# SWJ_v1_0.net
KiCad netlist of a schematic drawn in Altium Designer
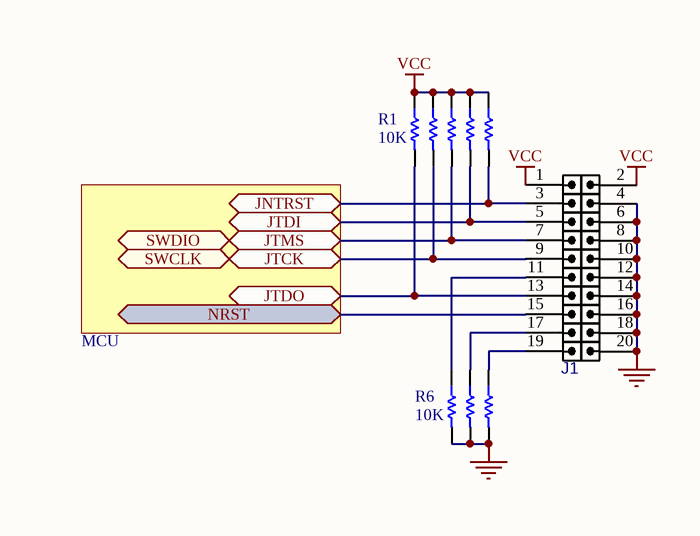
[diagram p0: SWJ_v1.0.SchDoc]

(export (version "E")
  (design (tool "Eeschema 10.0.6"))
  (components
    (comp (ref "J1")
      (value "Connector_2x10Pin_Male")
      (footprint "IDC_THD_P2.54_2X10")
      (description "Connector, Header")
      (fields (field (name "1_PART NUMBER") "TST-115-04-G-D-RA"))
      (libsource (lib "Connector") (part "Connector_2x10Pin_Male"))
    )
    (comp (ref "R1")
      (value "10K")
      (footprint "SMD_0805")
      (description "Resistor, 1/4W, 5%")
      (libsource (lib "General") (part "Resistor"))
    )
    (comp (ref "R2")
      (value "10K")
      (footprint "SMD_0805")
      (description "Resistor, 1/4W, 5%")
      (libsource (lib "General") (part "Resistor"))
    )
    (comp (ref "R3")
      (value "10K")
      (footprint "SMD_0805")
      (description "Resistor, 1/4W, 5%")
      (libsource (lib "General") (part "Resistor"))
    )
    (comp (ref "R4")
      (value "10K")
      (footprint "SMD_0805")
      (description "Resistor, 1/4W, 5%")
      (libsource (lib "General") (part "Resistor"))
    )
    (comp (ref "R5")
      (value "10K")
      (footprint "SMD_0805")
      (description "Resistor, 1/4W, 5%")
      (libsource (lib "General") (part "Resistor"))
    )
    (comp (ref "R6")
      (value "10K")
      (footprint "SMD_0805")
      (description "Resistor, 1/4W, 5%")
      (libsource (lib "General") (part "Resistor"))
    )
    (comp (ref "R7")
      (value "10K")
      (footprint "SMD_0805")
      (description "Resistor, 1/4W, 5%")
      (libsource (lib "General") (part "Resistor"))
    )
    (comp (ref "R8")
      (value "10K")
      (footprint "SMD_0805")
      (description "Resistor, 1/4W, 5%")
      (libsource (lib "General") (part "Resistor"))
    )
  )
  (nets
    (net (code "1") (name "/JNTRST") (class "Default")
      (node (ref "J1") (pin "3") (pinfunction "3_3") (pintype "passive"))
      (node (ref "R5") (pin "1") (pinfunction "1_1") (pintype "passive"))
    )
    (net (code "2") (name "/JTCK") (class "Default")
      (node (ref "J1") (pin "9") (pinfunction "9_9") (pintype "passive"))
      (node (ref "R2") (pin "1") (pinfunction "1_1") (pintype "passive"))
    )
    (net (code "3") (name "/JTDI") (class "Default")
      (node (ref "J1") (pin "5") (pinfunction "5_5") (pintype "passive"))
      (node (ref "R4") (pin "1") (pinfunction "1_1") (pintype "passive"))
    )
    (net (code "4") (name "/JTDO") (class "Default")
      (node (ref "J1") (pin "13") (pinfunction "13_13") (pintype "passive"))
      (node (ref "R1") (pin "1") (pinfunction "1_1") (pintype "passive"))
    )
    (net (code "5") (name "/JTMS") (class "Default")
      (node (ref "J1") (pin "7") (pinfunction "7_7") (pintype "passive"))
      (node (ref "R3") (pin "1") (pinfunction "1_1") (pintype "passive"))
    )
    (net (code "6") (name "/NRST") (class "Default")
      (node (ref "J1") (pin "15") (pinfunction "15_15") (pintype "passive"))
    )
    (net (code "9") (name "GND") (class "Default")
      (node (ref "J1") (pin "10") (pinfunction "10_10") (pintype "passive"))
      (node (ref "J1") (pin "12") (pinfunction "12_12") (pintype "passive"))
      (node (ref "J1") (pin "14") (pinfunction "14_14") (pintype "passive"))
      (node (ref "J1") (pin "16") (pinfunction "16_16") (pintype "passive"))
      (node (ref "J1") (pin "18") (pinfunction "18_18") (pintype "passive"))
      (node (ref "J1") (pin "20") (pinfunction "20_20") (pintype "passive"))
      (node (ref "J1") (pin "4") (pinfunction "4_4") (pintype "passive"))
      (node (ref "J1") (pin "6") (pinfunction "6_6") (pintype "passive"))
      (node (ref "J1") (pin "8") (pinfunction "8_8") (pintype "passive"))
      (node (ref "R6") (pin "1") (pinfunction "1_1") (pintype "passive"))
      (node (ref "R7") (pin "1") (pinfunction "1_1") (pintype "passive"))
      (node (ref "R8") (pin "1") (pinfunction "1_1") (pintype "passive"))
    )
    (net (code "10") (name "Net-(J1-Pad11)") (class "Default")
      (node (ref "J1") (pin "11") (pinfunction "11_11") (pintype "passive"))
      (node (ref "R6") (pin "2") (pinfunction "2_2") (pintype "passive"))
    )
    (net (code "11") (name "Net-(J1-Pad17)") (class "Default")
      (node (ref "J1") (pin "17") (pinfunction "17_17") (pintype "passive"))
      (node (ref "R7") (pin "2") (pinfunction "2_2") (pintype "passive"))
    )
    (net (code "12") (name "Net-(J1-Pad19)") (class "Default")
      (node (ref "J1") (pin "19") (pinfunction "19_19") (pintype "passive"))
      (node (ref "R8") (pin "2") (pinfunction "2_2") (pintype "passive"))
    )
    (net (code "13") (name "VCC") (class "Default")
      (node (ref "J1") (pin "1") (pinfunction "1_1") (pintype "passive"))
      (node (ref "J1") (pin "2") (pinfunction "2_2") (pintype "passive"))
      (node (ref "R1") (pin "2") (pinfunction "2_2") (pintype "passive"))
      (node (ref "R2") (pin "2") (pinfunction "2_2") (pintype "passive"))
      (node (ref "R3") (pin "2") (pinfunction "2_2") (pintype "passive"))
      (node (ref "R4") (pin "2") (pinfunction "2_2") (pintype "passive"))
      (node (ref "R5") (pin "2") (pinfunction "2_2") (pintype "passive"))
    )
  )
)
